# 4_Channel_TVS.net
KiCad netlist of a schematic drawn in Altium Designer
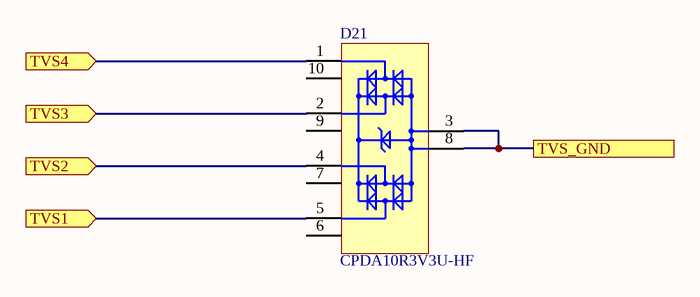
[diagram p0: 4_Channel_TVS.SchDoc]

(export (version "E")
  (design (tool "Eeschema 10.0.6"))
  (components
    (comp (ref "D21")
      (value "CPDA10R3V3U-HF")
      (footprint "DFN230X100X55X10N")
      (fields (field (name "VOLTAGE") "3.3V"))
      (libsource (lib "TE") (part "DIODE_ARR_10N_1"))
    )
  )
  (nets
    (net (code "1") (name "/TVS1") (class "Default")
      (node (ref "D21") (pin "5") (pinfunction "5_5") (pintype "passive"))
    )
    (net (code "2") (name "/TVS2") (class "Default")
      (node (ref "D21") (pin "4") (pinfunction "4_4") (pintype "passive"))
    )
    (net (code "3") (name "/TVS3") (class "Default")
      (node (ref "D21") (pin "2") (pinfunction "2_2") (pintype "passive"))
    )
    (net (code "4") (name "/TVS4") (class "Default")
      (node (ref "D21") (pin "1") (pinfunction "1_1") (pintype "passive"))
    )
    (net (code "5") (name "/TVS_GND") (class "Default")
      (node (ref "D21") (pin "3") (pinfunction "3_3") (pintype "passive"))
      (node (ref "D21") (pin "8") (pinfunction "8_8") (pintype "passive"))
    )
    (net (code "6") (name "unconnected-(D21-Pad6)") (class "Default")
      (node (ref "D21") (pin "6") (pinfunction "6_6") (pintype "passive"))
    )
    (net (code "7") (name "unconnected-(D21-Pad7)") (class "Default")
      (node (ref "D21") (pin "7") (pinfunction "7_7") (pintype "passive"))
    )
    (net (code "8") (name "unconnected-(D21-Pad9)") (class "Default")
      (node (ref "D21") (pin "9") (pinfunction "9_9") (pintype "passive"))
    )
    (net (code "9") (name "unconnected-(D21-Pad10)") (class "Default")
      (node (ref "D21") (pin "10") (pinfunction "10_10") (pintype "passive"))
    )
  )
)
